# NHD-1_27-12896UGC3.net
KiCad netlist of a schematic drawn in Altium Designer
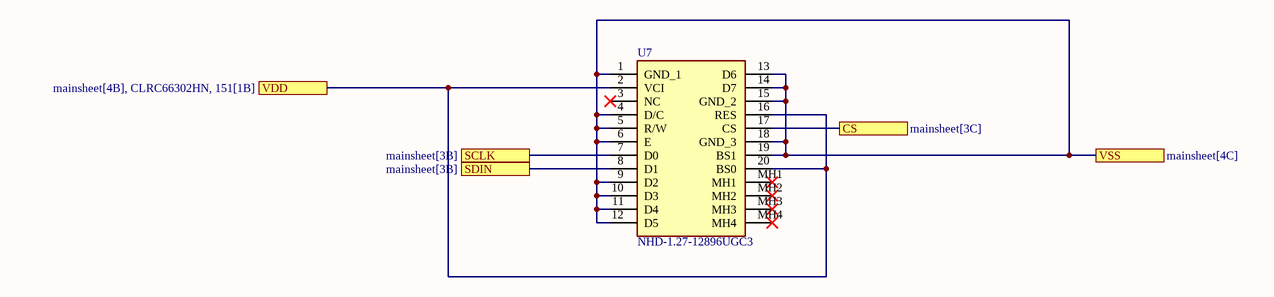
[diagram p0: NHD-1.27-12896UGC3.SchDoc]

(export (version "E")
  (design (tool "Eeschema 10.0.6"))
  (components
    (comp (ref "U7")
      (value "NHD-1.27-12896UGC3")
      (footprint "PcbLib1:NHD12712896UGC3")
      (description "Display")
      (fields (field (name "MOUSER PART NUMBER") "763-NHD1.2712896UGC3"))
      (libsource (lib "*") (part "NHD-1.27-12896UGC3"))
    )
  )
  (nets
    (net (code "1") (name "/CS") (class "Default")
      (node (ref "U7") (pin "17") (pinfunction "CS_17") (pintype "passive"))
    )
    (net (code "2") (name "/SCLK") (class "Default")
      (node (ref "U7") (pin "7") (pinfunction "D0_7") (pintype "passive"))
    )
    (net (code "3") (name "/SDIN") (class "Default")
      (node (ref "U7") (pin "8") (pinfunction "D1_8") (pintype "passive"))
    )
    (net (code "4") (name "/VDD") (class "Default")
      (node (ref "U7") (pin "16") (pinfunction "RES_16") (pintype "passive"))
      (node (ref "U7") (pin "2") (pinfunction "VCI_2") (pintype "passive"))
      (node (ref "U7") (pin "20") (pinfunction "BS0_20") (pintype "passive"))
    )
    (net (code "5") (name "/VSS") (class "Default")
      (node (ref "U7") (pin "1") (pinfunction "GND_1_1") (pintype "passive"))
      (node (ref "U7") (pin "10") (pinfunction "D3_10") (pintype "passive"))
      (node (ref "U7") (pin "11") (pinfunction "D4_11") (pintype "passive"))
      (node (ref "U7") (pin "12") (pinfunction "D5_12") (pintype "passive"))
      (node (ref "U7") (pin "13") (pinfunction "D6_13") (pintype "passive"))
      (node (ref "U7") (pin "14") (pinfunction "D7_14") (pintype "passive"))
      (node (ref "U7") (pin "15") (pinfunction "GND_2_15") (pintype "passive"))
      (node (ref "U7") (pin "18") (pinfunction "GND_3_18") (pintype "passive"))
      (node (ref "U7") (pin "19") (pinfunction "BS1_19") (pintype "passive"))
      (node (ref "U7") (pin "4") (pinfunction "D/C_4") (pintype "passive"))
      (node (ref "U7") (pin "5") (pinfunction "R/W_5") (pintype "passive"))
      (node (ref "U7") (pin "6") (pinfunction "E_6") (pintype "passive"))
      (node (ref "U7") (pin "9") (pinfunction "D2_9") (pintype "passive"))
    )
    (net (code "6") (name "unconnected-(U7-NC-Pad3)") (class "Default")
      (node (ref "U7") (pin "3") (pinfunction "NC_3") (pintype "passive+no_connect"))
    )
    (net (code "7") (name "unconnected-(U7-PadMH1)") (class "Default")
      (node (ref "U7") (pin "MH1") (pinfunction "MH1_MH1") (pintype "passive+no_connect"))
    )
    (net (code "8") (name "unconnected-(U7-PadMH2)") (class "Default")
      (node (ref "U7") (pin "MH2") (pinfunction "MH2_MH2") (pintype "passive+no_connect"))
    )
    (net (code "9") (name "unconnected-(U7-PadMH3)") (class "Default")
      (node (ref "U7") (pin "MH3") (pinfunction "MH3_MH3") (pintype "passive+no_connect"))
    )
    (net (code "10") (name "unconnected-(U7-PadMH4)") (class "Default")
      (node (ref "U7") (pin "MH4") (pinfunction "MH4_MH4") (pintype "passive+no_connect"))
    )
  )
)
